# LuminchOne.net
KiCad netlist of a schematic drawn in EAGLE
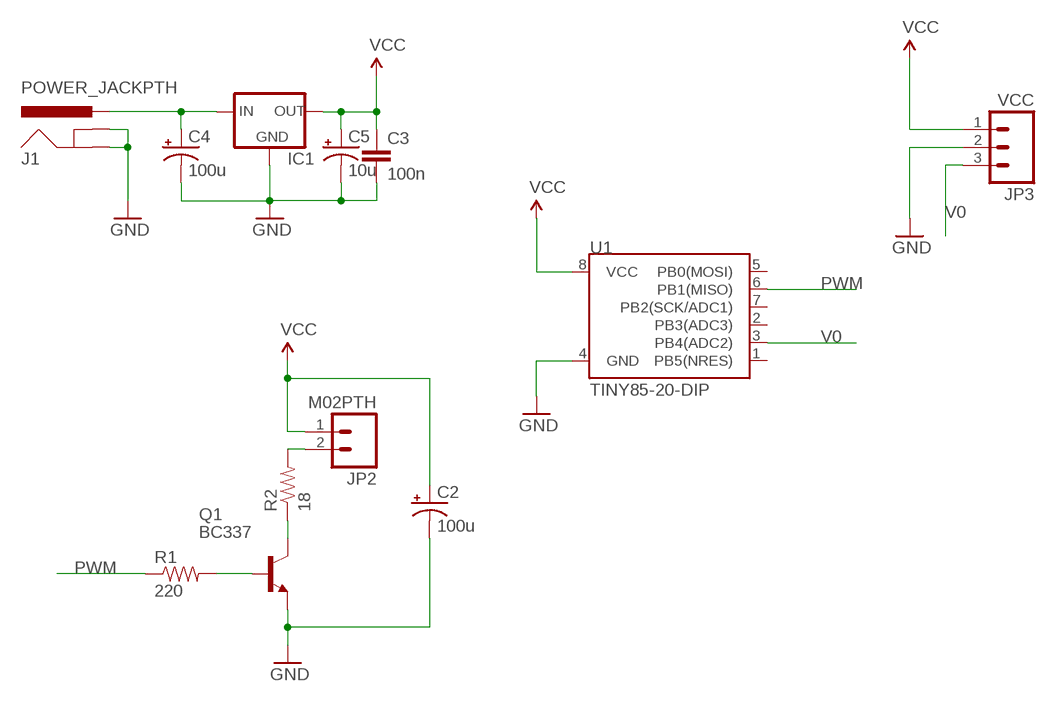
[diagram p0: schematic, sheet 1]

(export (version "E")
  (design (tool "Eeschema 10.0.6"))
  (components
    (comp (ref "C2")
      (value "100u")
      (footprint "eagle-import:CPOL-RADIAL-100UF-25V")
      (libsource (lib "eagle-import") (part "CAP_POLPTH1"))
    )
    (comp (ref "C3")
      (value "100n")
      (footprint "eagle-import:CAP-PTH-SMALL")
      (libsource (lib "eagle-import") (part "CAPPTH"))
    )
    (comp (ref "C4")
      (value "100u")
      (footprint "eagle-import:CPOL-RADIAL-100UF-25V")
      (libsource (lib "eagle-import") (part "CAP_POLPTH1"))
    )
    (comp (ref "C5")
      (value "10u")
      (footprint "eagle-import:CPOL-RADIAL-10UF-25V")
      (libsource (lib "eagle-import") (part "CAP_POLPTH2"))
    )
    (comp (ref "IC1")
      (value "V_REG_78XX-TO-220")
      (footprint "eagle-import:TO-220-ALT")
      (libsource (lib "eagle-import") (part "V_REG_78XX-TO-220"))
    )
    (comp (ref "J1")
      (value "POWER_JACKPTH")
      (footprint "eagle-import:POWER_JACK_PTH")
      (libsource (lib "eagle-import") (part "POWER_JACKPTH"))
    )
    (comp (ref "JP2")
      (value "M02PTH")
      (footprint "eagle-import:1X02")
      (libsource (lib "eagle-import") (part "M02PTH"))
    )
    (comp (ref "JP3")
      (value "VCC")
      (footprint "eagle-import:1X03")
      (libsource (lib "eagle-import") (part "M03PTH"))
    )
    (comp (ref "Q1")
      (value "BC337")
      (footprint "eagle-import:TO92")
      (libsource (lib "eagle-import") (part "BC337"))
    )
    (comp (ref "R1")
      (value "220")
      (footprint "eagle-import:AXIAL-0.4")
      (libsource (lib "eagle-import") (part "RESISTORPTH-1/4W"))
    )
    (comp (ref "R2")
      (value "18")
      (footprint "eagle-import:AXIAL-0.6")
      (libsource (lib "eagle-import") (part "RESISTORPTH-1W"))
    )
    (comp (ref "U1")
      (value "TINY85-20-DIP")
      (footprint "eagle-import:DIP08")
      (libsource (lib "eagle-import") (part "ATTINY45TINY85-20-DIP"))
    )
  )
  (nets
    (net (code "1") (name "/PWM") (class "Default")
      (node (ref "R1") (pin "P$1") (pinfunction "1_P$1") (pintype "passive"))
      (node (ref "U1") (pin "6") (pinfunction "PB1(MISO)_6") (pintype "bidirectional"))
    )
    (net (code "2") (name "/V0") (class "Default")
      (node (ref "JP3") (pin "3") (pinfunction "3_3") (pintype "passive"))
      (node (ref "U1") (pin "3") (pinfunction "PB4(ADC2)_3") (pintype "bidirectional"))
    )
    (net (code "3") (name "GND") (class "Default")
      (node (ref "C2") (pin "2") (pinfunction "-_2") (pintype "passive"))
      (node (ref "C3") (pin "2") (pinfunction "2_2") (pintype "passive"))
      (node (ref "C4") (pin "2") (pinfunction "-_2") (pintype "passive"))
      (node (ref "C5") (pin "2") (pinfunction "-_2") (pintype "passive"))
      (node (ref "IC1") (pin "GND") (pinfunction "GND_GND") (pintype "input"))
      (node (ref "J1") (pin "GND") (pinfunction "GND_GND") (pintype "bidirectional"))
      (node (ref "J1") (pin "GNDBREAK") (pinfunction "GNDBREAK_GNDBREAK") (pintype "bidirectional"))
      (node (ref "JP3") (pin "2") (pinfunction "2_2") (pintype "passive"))
      (node (ref "Q1") (pin "1") (pinfunction "E_1") (pintype "passive"))
      (node (ref "U1") (pin "4") (pinfunction "GND_4") (pintype "bidirectional"))
    )
    (net (code "4") (name "Net-(C4-+)") (class "Default")
      (node (ref "C4") (pin "1") (pinfunction "+_1") (pintype "passive"))
      (node (ref "IC1") (pin "IN") (pinfunction "IN_IN") (pintype "input"))
      (node (ref "J1") (pin "PWR") (pinfunction "PWR_PWR") (pintype "bidirectional"))
    )
    (net (code "5") (name "Net-(Q1-B)") (class "Default")
      (node (ref "Q1") (pin "2") (pinfunction "B_2") (pintype "passive"))
      (node (ref "R1") (pin "P$2") (pinfunction "2_P$2") (pintype "passive"))
    )
    (net (code "6") (name "Net-(Q1-C)") (class "Default")
      (node (ref "Q1") (pin "3") (pinfunction "C_3") (pintype "passive"))
      (node (ref "R2") (pin "P$1") (pinfunction "1_P$1") (pintype "passive"))
    )
    (net (code "7") (name "Net-(R2-2)") (class "Default")
      (node (ref "JP2") (pin "2") (pinfunction "2_2") (pintype "passive"))
      (node (ref "R2") (pin "P$2") (pinfunction "2_P$2") (pintype "passive"))
    )
    (net (code "8") (name "VCC") (class "Default")
      (node (ref "C2") (pin "1") (pinfunction "+_1") (pintype "passive"))
      (node (ref "C3") (pin "1") (pinfunction "1_1") (pintype "passive"))
      (node (ref "C5") (pin "1") (pinfunction "+_1") (pintype "passive"))
      (node (ref "IC1") (pin "OUT") (pinfunction "OUT_OUT") (pintype "output"))
      (node (ref "JP2") (pin "1") (pinfunction "1_1") (pintype "passive"))
      (node (ref "JP3") (pin "1") (pinfunction "1_1") (pintype "passive"))
      (node (ref "U1") (pin "8") (pinfunction "VCC_8") (pintype "bidirectional"))
    )
    (net (code "9") (name "unconnected-(U1-PB0(MOSI)-Pad5)") (class "Default")
      (node (ref "U1") (pin "5") (pinfunction "PB0(MOSI)_5") (pintype "bidirectional"))
    )
    (net (code "10") (name "unconnected-(U1-PB2(SCK{slash}ADC1)-Pad7)") (class "Default")
      (node (ref "U1") (pin "7") (pinfunction "PB2(SCK/ADC1)_7") (pintype "bidirectional"))
    )
    (net (code "11") (name "unconnected-(U1-PB3(ADC3)-Pad2)") (class "Default")
      (node (ref "U1") (pin "2") (pinfunction "PB3(ADC3)_2") (pintype "bidirectional"))
    )
    (net (code "12") (name "unconnected-(U1-PB5(NRES)-Pad1)") (class "Default")
      (node (ref "U1") (pin "1") (pinfunction "PB5(NRES)_1") (pintype "bidirectional"))
    )
  )
)
